# ESP12_Low_Power.net
KiCad netlist of a schematic drawn in EAGLE
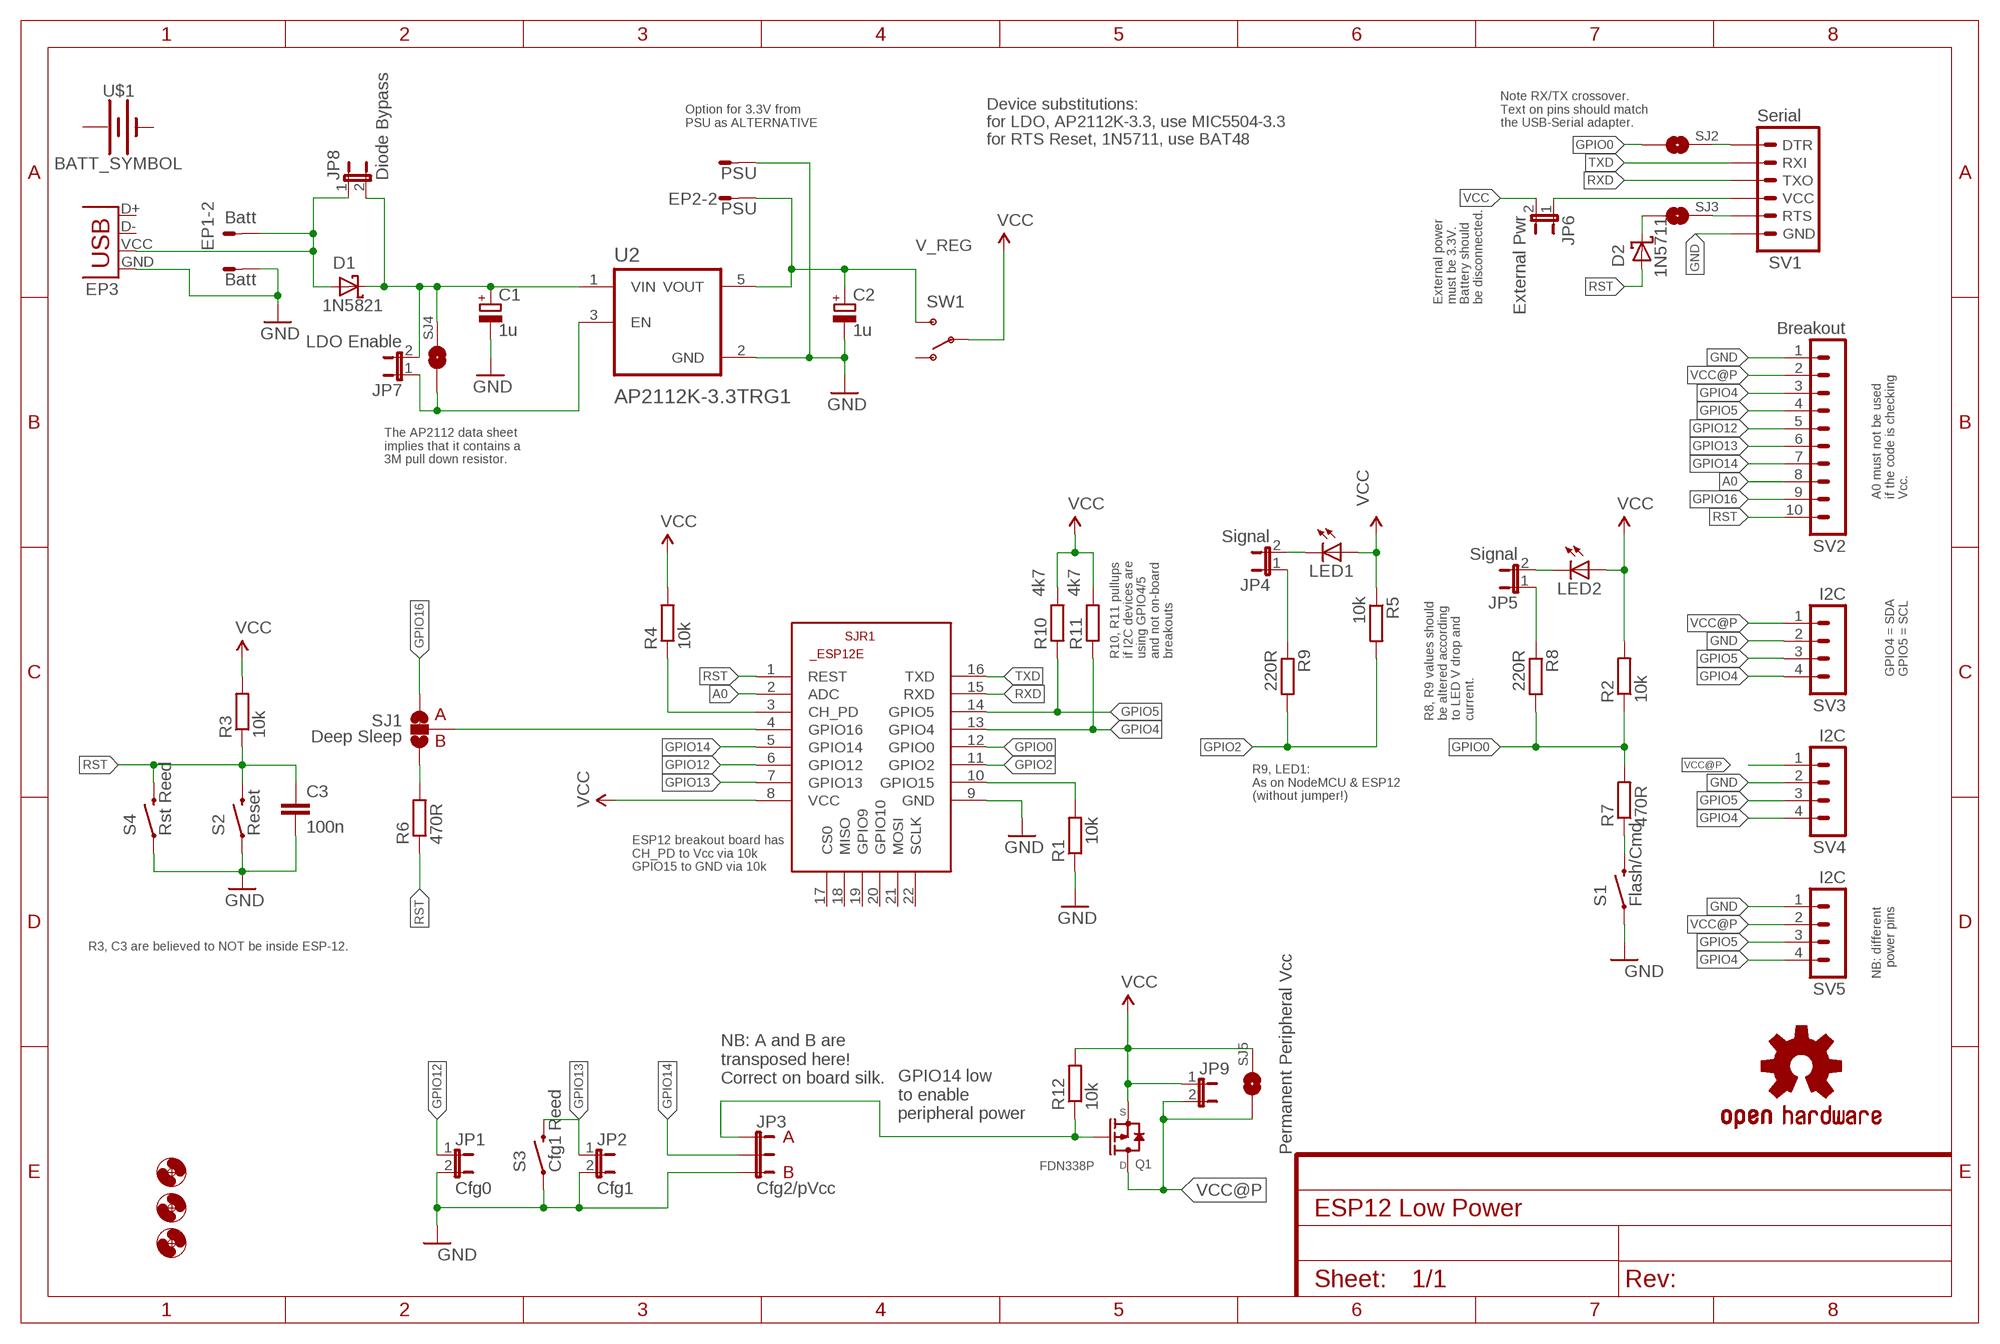
[diagram p0: schematic, sheet 1]

(export (version "E")
  (design (tool "Eeschema 10.0.6"))
  (components
    (comp (ref "C1")
      (value "1u")
      (footprint "eagle-import:E2,5-5")
      (libsource (lib "eagle-import") (part "CPOL-EUE2.5-510UF"))
    )
    (comp (ref "C2")
      (value "1u")
      (footprint "eagle-import:E2,5-5")
      (libsource (lib "eagle-import") (part "CPOL-EUE2.5-510UF"))
    )
    (comp (ref "C3")
      (value "100n")
      (footprint "eagle-import:1206")
      (libsource (lib "eagle-import") (part "C-EU1206"))
    )
    (comp (ref "D1")
      (value "1N5821")
      (footprint "eagle-import:DO201-15")
      (libsource (lib "eagle-import") (part "DIODE-SCHOTTKYDO-201-VERT"))
    )
    (comp (ref "D2")
      (value "1N5711")
      (footprint "eagle-import:DO35-7")
      (libsource (lib "eagle-import") (part "DIODE-SCHOTTKYDO35-7"))
    )
    (comp (ref "EP1")
      (value "Batt")
      (footprint "eagle-import:02P")
      (libsource (lib "eagle-import") (part "M02S"))
    )
    (comp (ref "EP2")
      (value "PSU")
      (footprint "eagle-import:02P")
      (libsource (lib "eagle-import") (part "M02S"))
    )
    (comp (ref "EP3")
      (value "USB-FCI_SMD***")
      (footprint "eagle-import:FCI_USB_B_SMD")
      (libsource (lib "eagle-import") (part "USB-FCI_SMD"))
    )
    (comp (ref "H1")
      (value "MOUNT-HOLE3.2")
      (footprint "eagle-import:3,2")
      (libsource (lib "eagle-import") (part "MOUNT-HOLE3.2"))
    )
    (comp (ref "H2")
      (value "MOUNT-HOLE3.2")
      (footprint "eagle-import:3,2")
      (libsource (lib "eagle-import") (part "MOUNT-HOLE3.2"))
    )
    (comp (ref "H4")
      (value "MOUNT-HOLE3.2")
      (footprint "eagle-import:3,2")
      (libsource (lib "eagle-import") (part "MOUNT-HOLE3.2"))
    )
    (comp (ref "JP1")
      (value "Cfg0")
      (footprint "eagle-import:1X02")
      (libsource (lib "eagle-import") (part "JUMPER-2PTH"))
    )
    (comp (ref "JP2")
      (value "Cfg1")
      (footprint "eagle-import:1X02")
      (libsource (lib "eagle-import") (part "JUMPER-2PTH"))
    )
    (comp (ref "JP3")
      (value "Cfg2/pVcc")
      (footprint "eagle-import:1X03_JMP")
      (libsource (lib "eagle-import") (part "JUMPER-3PTH"))
    )
    (comp (ref "JP4")
      (value "Signal")
      (footprint "eagle-import:1X02")
      (libsource (lib "eagle-import") (part "JUMPER-2PTH"))
    )
    (comp (ref "JP5")
      (value "Signal")
      (footprint "eagle-import:1X02")
      (libsource (lib "eagle-import") (part "JUMPER-2PTH"))
    )
    (comp (ref "JP6")
      (value "External Pwr")
      (footprint "eagle-import:1X02")
      (libsource (lib "eagle-import") (part "JUMPER-2PTH"))
    )
    (comp (ref "JP7")
      (value "LDO Enable")
      (footprint "eagle-import:1X02")
      (libsource (lib "eagle-import") (part "JUMPER-2PTH"))
    )
    (comp (ref "JP8")
      (value "Diode Bypass")
      (footprint "eagle-import:1X02")
      (libsource (lib "eagle-import") (part "JUMPER-2PTH"))
    )
    (comp (ref "JP9")
      (value "Permanent Peripheral Vcc")
      (footprint "eagle-import:1X02")
      (libsource (lib "eagle-import") (part "JUMPER-2PTH"))
    )
    (comp (ref "LED1")
      (value "LED1206")
      (footprint "eagle-import:LED-1206")
      (libsource (lib "eagle-import") (part "LED1206"))
    )
    (comp (ref "LED2")
      (value "LED1206")
      (footprint "eagle-import:LED-1206")
      (libsource (lib "eagle-import") (part "LED1206"))
    )
    (comp (ref "LOGO1")
      (value "OSHW-LOGOM")
      (footprint "eagle-import:OSHW-LOGO-M")
      (libsource (lib "eagle-import") (part "OSHW-LOGOM"))
    )
    (comp (ref "Q1")
      (value "FDN338P")
      (footprint "eagle-import:SOT23")
      (libsource (lib "eagle-import") (part "FDN338P_PMOS-SOT23"))
    )
    (comp (ref "R1")
      (value "10k")
      (footprint "eagle-import:1206")
      (libsource (lib "eagle-import") (part "R-EU_"))
    )
    (comp (ref "R2")
      (value "10k")
      (footprint "eagle-import:1206")
      (libsource (lib "eagle-import") (part "R-EU_"))
    )
    (comp (ref "R3")
      (value "10k")
      (footprint "eagle-import:1206")
      (libsource (lib "eagle-import") (part "R-EU_"))
    )
    (comp (ref "R4")
      (value "10k")
      (footprint "eagle-import:1206")
      (libsource (lib "eagle-import") (part "R-EU_"))
    )
    (comp (ref "R5")
      (value "10k")
      (footprint "eagle-import:1206")
      (libsource (lib "eagle-import") (part "R-EU_"))
    )
    (comp (ref "R6")
      (value "470R")
      (footprint "eagle-import:0204_7")
      (libsource (lib "eagle-import") (part "R-EU_0204/7"))
    )
    (comp (ref "R7")
      (value "470R")
      (footprint "eagle-import:0204_7")
      (libsource (lib "eagle-import") (part "R-EU_0204/7"))
    )
    (comp (ref "R8")
      (value "220R")
      (footprint "eagle-import:0204_7")
      (libsource (lib "eagle-import") (part "R-EU_0204/7"))
    )
    (comp (ref "R9")
      (value "220R")
      (footprint "eagle-import:0204_7")
      (libsource (lib "eagle-import") (part "R-EU_0204/7"))
    )
    (comp (ref "R10")
      (value "4k7")
      (footprint "eagle-import:1206")
      (libsource (lib "eagle-import") (part "R-EU_"))
    )
    (comp (ref "R11")
      (value "4k7")
      (footprint "eagle-import:1206")
      (libsource (lib "eagle-import") (part "R-EU_"))
    )
    (comp (ref "R12")
      (value "10k")
      (footprint "eagle-import:0204_7")
      (libsource (lib "eagle-import") (part "R-EU_0204/7"))
    )
    (comp (ref "S1")
      (value "Flash/Cmd")
      (footprint "eagle-import:TACTILE-PTH")
      (libsource (lib "eagle-import") (part "SWITCH-MOMENTARY-2PTH"))
    )
    (comp (ref "S2")
      (value "Reset")
      (footprint "eagle-import:TACTILE-PTH")
      (libsource (lib "eagle-import") (part "SWITCH-MOMENTARY-2PTH"))
    )
    (comp (ref "S3")
      (value "Cfg1 Reed")
      (footprint "eagle-import:REED_SWITCH_PTH")
      (libsource (lib "eagle-import") (part "SWITCH-MOMENTARY-2PTH_REED"))
    )
    (comp (ref "S4")
      (value "Rst Reed")
      (footprint "eagle-import:REED_SWITCH_PTH")
      (libsource (lib "eagle-import") (part "SWITCH-MOMENTARY-2PTH_REED"))
    )
    (comp (ref "SJ1")
      (value "Deep Sleep")
      (footprint "eagle-import:SJ_3")
      (libsource (lib "eagle-import") (part "SOLDERJUMPER_2WAYSJ_3_TRACE"))
    )
    (comp (ref "SJ2")
      (value "SOLDERJUMPERTRACE")
      (footprint "eagle-import:SJ_2S-TRACE")
      (libsource (lib "eagle-import") (part "SOLDERJUMPERTRACE"))
    )
    (comp (ref "SJ3")
      (value "SOLDERJUMPERTRACE")
      (footprint "eagle-import:SJ_2S-TRACE")
      (libsource (lib "eagle-import") (part "SOLDERJUMPERTRACE"))
    )
    (comp (ref "SJ4")
      (value "SOLDERJUMPERTRACE")
      (footprint "eagle-import:SJ_2S-TRACE")
      (libsource (lib "eagle-import") (part "SOLDERJUMPERTRACE"))
    )
    (comp (ref "SJ5")
      (value "SOLDERJUMPERTRACE")
      (footprint "eagle-import:SJ_2S-TRACE")
      (libsource (lib "eagle-import") (part "SOLDERJUMPERTRACE"))
    )
    (comp (ref "SJR1")
      (value "ESP8266-12EESP12E")
      (footprint "eagle-import:ESP8266-ESP12E")
      (libsource (lib "eagle-import") (part "ESP8266-12EESP12E"))
    )
    (comp (ref "SV1")
      (value "Serial")
      (footprint "eagle-import:1X06-KIT")
      (libsource (lib "eagle-import") (part "ESP8266_SERIAL_PROGRAM1X06_ESP_SERIAL"))
    )
    (comp (ref "SV2")
      (value "Breakout")
      (footprint "eagle-import:MA10-1")
      (libsource (lib "eagle-import") (part "HEADER-1X10P"))
    )
    (comp (ref "SV3")
      (value "I2C")
      (footprint "eagle-import:MA04-1")
      (libsource (lib "eagle-import") (part "MA04-1"))
    )
    (comp (ref "SV4")
      (value "I2C")
      (footprint "eagle-import:MA04-1")
      (libsource (lib "eagle-import") (part "MA04-1"))
    )
    (comp (ref "SV5")
      (value "I2C")
      (footprint "eagle-import:MA04-1")
      (libsource (lib "eagle-import") (part "MA04-1"))
    )
    (comp (ref "SW1")
      (value "SWITCH_SPDTMULTICOMP_MS2")
      (footprint "eagle-import:MULTICOMP_2MS")
      (libsource (lib "eagle-import") (part "SWITCH_SPDTMULTICOMP_MS2"))
    )
    (comp (ref "U$1")
      (value "BATT_SYMBOL")
      (footprint "eagle-import:BATTERY_18650-HOLDER_SILK")
      (libsource (lib "eagle-import") (part "BATT_SYMBOL"))
    )
    (comp (ref "U2")
      (value "AP2112K-3.3TRG1")
      (footprint "eagle-import:SOT95P285X140-5N")
      (fields (field (name "MF") "Diodes Inc."))
      (libsource (lib "eagle-import") (part "AP2112K-3.3TRG1"))
    )
  )
  (nets
    (net (code "1") (name "/V_REG") (class "Default")
      (node (ref "C2") (pin "+") (pinfunction "+_+") (pintype "passive"))
      (node (ref "EP2") (pin "2") (pinfunction "S_2") (pintype "passive"))
      (node (ref "SW1") (pin "P$3") (pinfunction "S_P$3") (pintype "passive"))
      (node (ref "U2") (pin "5") (pinfunction "VOUT_5") (pintype "power_in"))
    )
    (net (code "2") (name "A0") (class "Default")
      (node (ref "SJR1") (pin "2") (pinfunction "ADC_2") (pintype "bidirectional"))
      (node (ref "SV2") (pin "8") (pinfunction "8_8") (pintype "passive"))
    )
    (net (code "3") (name "GND") (class "Default")
      (node (ref "C1") (pin "-") (pinfunction "-_-") (pintype "passive"))
      (node (ref "C2") (pin "-") (pinfunction "-_-") (pintype "passive"))
      (node (ref "C3") (pin "2") (pinfunction "2_2") (pintype "passive"))
      (node (ref "EP1") (pin "2") (pinfunction "S_2") (pintype "passive"))
      (node (ref "EP2") (pin "1") (pinfunction "S_1") (pintype "passive"))
      (node (ref "EP3") (pin "GND") (pinfunction "GND_GND") (pintype "bidirectional"))
      (node (ref "JP1") (pin "2") (pinfunction "2_2") (pintype "passive"))
      (node (ref "JP2") (pin "2") (pinfunction "2_2") (pintype "passive"))
      (node (ref "JP3") (pin "3") (pinfunction "3_3") (pintype "passive"))
      (node (ref "R1") (pin "1") (pinfunction "1_1") (pintype "passive"))
      (node (ref "S1") (pin "1") (pinfunction "1_1") (pintype "passive"))
      (node (ref "S2") (pin "1") (pinfunction "1_1") (pintype "passive"))
      (node (ref "S3") (pin "P$1") (pinfunction "1_P$1") (pintype "passive"))
      (node (ref "S4") (pin "P$1") (pinfunction "1_P$1") (pintype "passive"))
      (node (ref "SJR1") (pin "9") (pinfunction "GND_9") (pintype "bidirectional"))
      (node (ref "SV1") (pin "1") (pinfunction "GND_1") (pintype "passive"))
      (node (ref "SV2") (pin "1") (pinfunction "1_1") (pintype "passive"))
      (node (ref "SV3") (pin "2") (pinfunction "2_2") (pintype "passive"))
      (node (ref "SV4") (pin "2") (pinfunction "2_2") (pintype "passive"))
      (node (ref "SV5") (pin "1") (pinfunction "1_1") (pintype "passive"))
      (node (ref "U2") (pin "2") (pinfunction "GND_2") (pintype "power_in"))
    )
    (net (code "4") (name "GPIO0") (class "Default")
      (node (ref "R2") (pin "1") (pinfunction "1_1") (pintype "passive"))
      (node (ref "R7") (pin "2") (pinfunction "2_2") (pintype "passive"))
      (node (ref "R8") (pin "2") (pinfunction "2_2") (pintype "passive"))
      (node (ref "SJ2") (pin "1") (pinfunction "1_1") (pintype "passive"))
      (node (ref "SJR1") (pin "12") (pinfunction "GPIO0_12") (pintype "bidirectional"))
    )
    (net (code "5") (name "GPIO2") (class "Default")
      (node (ref "R5") (pin "2") (pinfunction "2_2") (pintype "passive"))
      (node (ref "R9") (pin "2") (pinfunction "2_2") (pintype "passive"))
      (node (ref "SJR1") (pin "11") (pinfunction "GPIO2_11") (pintype "bidirectional"))
    )
    (net (code "6") (name "GPIO4") (class "Default")
      (node (ref "R11") (pin "1") (pinfunction "1_1") (pintype "passive"))
      (node (ref "SJR1") (pin "13") (pinfunction "GPIO4_13") (pintype "bidirectional"))
      (node (ref "SV2") (pin "3") (pinfunction "3_3") (pintype "passive"))
      (node (ref "SV3") (pin "4") (pinfunction "4_4") (pintype "passive"))
      (node (ref "SV4") (pin "4") (pinfunction "4_4") (pintype "passive"))
      (node (ref "SV5") (pin "4") (pinfunction "4_4") (pintype "passive"))
    )
    (net (code "7") (name "GPIO5") (class "Default")
      (node (ref "R10") (pin "1") (pinfunction "1_1") (pintype "passive"))
      (node (ref "SJR1") (pin "14") (pinfunction "GPIO5_14") (pintype "bidirectional"))
      (node (ref "SV2") (pin "4") (pinfunction "4_4") (pintype "passive"))
      (node (ref "SV3") (pin "3") (pinfunction "3_3") (pintype "passive"))
      (node (ref "SV4") (pin "3") (pinfunction "3_3") (pintype "passive"))
      (node (ref "SV5") (pin "3") (pinfunction "3_3") (pintype "passive"))
    )
    (net (code "8") (name "GPIO12") (class "Default")
      (node (ref "JP1") (pin "1") (pinfunction "1_1") (pintype "passive"))
      (node (ref "SJR1") (pin "6") (pinfunction "GPIO12_6") (pintype "bidirectional"))
      (node (ref "SV2") (pin "5") (pinfunction "5_5") (pintype "passive"))
    )
    (net (code "9") (name "GPIO13") (class "Default")
      (node (ref "JP2") (pin "1") (pinfunction "1_1") (pintype "passive"))
      (node (ref "S3") (pin "P$2") (pinfunction "2_P$2") (pintype "passive"))
      (node (ref "SJR1") (pin "7") (pinfunction "GPIO13_7") (pintype "bidirectional"))
      (node (ref "SV2") (pin "6") (pinfunction "6_6") (pintype "passive"))
    )
    (net (code "10") (name "GPIO14") (class "Default")
      (node (ref "JP3") (pin "2") (pinfunction "2_2") (pintype "passive"))
      (node (ref "SJR1") (pin "5") (pinfunction "GPIO14_5") (pintype "bidirectional"))
      (node (ref "SV2") (pin "7") (pinfunction "7_7") (pintype "passive"))
    )
    (net (code "11") (name "GPIO16") (class "Default")
      (node (ref "SJ1") (pin "1") (pinfunction "1_1") (pintype "passive"))
      (node (ref "SV2") (pin "9") (pinfunction "9_9") (pintype "passive"))
    )
    (net (code "12") (name "Net-(D2-PadC)") (class "Default")
      (node (ref "D2") (pin "C") (pinfunction "C_C") (pintype "passive"))
      (node (ref "SJ3") (pin "1") (pinfunction "1_1") (pintype "passive"))
    )
    (net (code "13") (name "Net-(EP1A-S)") (class "Default")
      (node (ref "D1") (pin "A") (pinfunction "A_A") (pintype "passive"))
      (node (ref "EP1") (pin "1") (pinfunction "S_1") (pintype "passive"))
      (node (ref "EP3") (pin "VCC") (pinfunction "VBUS_VCC") (pintype "bidirectional"))
      (node (ref "JP8") (pin "1") (pinfunction "1_1") (pintype "passive"))
    )
    (net (code "14") (name "Net-(JP4-Pad1)") (class "Default")
      (node (ref "JP4") (pin "1") (pinfunction "1_1") (pintype "passive"))
      (node (ref "R9") (pin "1") (pinfunction "1_1") (pintype "passive"))
    )
    (net (code "15") (name "Net-(JP4-Pad2)") (class "Default")
      (node (ref "JP4") (pin "2") (pinfunction "2_2") (pintype "passive"))
      (node (ref "LED1") (pin "C") (pinfunction "C_C") (pintype "passive"))
    )
    (net (code "16") (name "Net-(JP5-Pad1)") (class "Default")
      (node (ref "JP5") (pin "1") (pinfunction "1_1") (pintype "passive"))
      (node (ref "R8") (pin "1") (pinfunction "1_1") (pintype "passive"))
    )
    (net (code "17") (name "Net-(JP5-Pad2)") (class "Default")
      (node (ref "JP5") (pin "2") (pinfunction "2_2") (pintype "passive"))
      (node (ref "LED2") (pin "C") (pinfunction "C_C") (pintype "passive"))
    )
    (net (code "18") (name "Net-(Q1-G)") (class "Default")
      (node (ref "JP3") (pin "1") (pinfunction "1_1") (pintype "passive"))
      (node (ref "Q1") (pin "1") (pinfunction "G_1") (pintype "passive"))
      (node (ref "R12") (pin "1") (pinfunction "1_1") (pintype "passive"))
    )
    (net (code "19") (name "Net-(R6-Pad2)") (class "Default")
      (node (ref "R6") (pin "2") (pinfunction "2_2") (pintype "passive"))
      (node (ref "SJ1") (pin "3") (pinfunction "3_3") (pintype "passive"))
    )
    (net (code "20") (name "Net-(S1-2)") (class "Default")
      (node (ref "R7") (pin "1") (pinfunction "1_1") (pintype "passive"))
      (node (ref "S1") (pin "3") (pinfunction "2_3") (pintype "passive"))
    )
    (net (code "21") (name "Net-(SJR1-CH_PD)") (class "Default")
      (node (ref "R4") (pin "1") (pinfunction "1_1") (pintype "passive"))
      (node (ref "SJR1") (pin "3") (pinfunction "CH_PD_3") (pintype "bidirectional"))
    )
    (net (code "22") (name "Net-(SJR1-GPIO15)") (class "Default")
      (node (ref "R1") (pin "2") (pinfunction "2_2") (pintype "passive"))
      (node (ref "SJR1") (pin "10") (pinfunction "GPIO15_10") (pintype "bidirectional"))
    )
    (net (code "23") (name "Net-(SJR1-GPIO16)") (class "Default")
      (node (ref "SJ1") (pin "2") (pinfunction "2_2") (pintype "passive"))
      (node (ref "SJR1") (pin "4") (pinfunction "GPIO16_4") (pintype "bidirectional"))
    )
    (net (code "24") (name "Net-(SV1-DTR)") (class "Default")
      (node (ref "SJ2") (pin "2") (pinfunction "2_2") (pintype "passive"))
      (node (ref "SV1") (pin "6") (pinfunction "DTR_6") (pintype "passive"))
    )
    (net (code "25") (name "Net-(SV1-RTS)") (class "Default")
      (node (ref "SJ3") (pin "2") (pinfunction "2_2") (pintype "passive"))
      (node (ref "SV1") (pin "2") (pinfunction "RTS_2") (pintype "passive"))
    )
    (net (code "26") (name "Net-(SV1-VCC)") (class "Default")
      (node (ref "JP6") (pin "1") (pinfunction "1_1") (pintype "passive"))
      (node (ref "SV1") (pin "3") (pinfunction "VCC_3") (pintype "passive"))
    )
    (net (code "27") (name "Net-(U2-EN)") (class "Default")
      (node (ref "JP7") (pin "1") (pinfunction "1_1") (pintype "passive"))
      (node (ref "SJ4") (pin "1") (pinfunction "1_1") (pintype "passive"))
      (node (ref "U2") (pin "3") (pinfunction "EN_3") (pintype "input"))
    )
    (net (code "28") (name "Net-(U2-VIN)") (class "Default")
      (node (ref "C1") (pin "+") (pinfunction "+_+") (pintype "passive"))
      (node (ref "D1") (pin "C") (pinfunction "C_C") (pintype "passive"))
      (node (ref "JP7") (pin "2") (pinfunction "2_2") (pintype "passive"))
      (node (ref "JP8") (pin "2") (pinfunction "2_2") (pintype "passive"))
      (node (ref "SJ4") (pin "2") (pinfunction "2_2") (pintype "passive"))
      (node (ref "U2") (pin "1") (pinfunction "VIN_1") (pintype "power_in"))
    )
    (net (code "29") (name "RST") (class "Default")
      (node (ref "C3") (pin "1") (pinfunction "1_1") (pintype "passive"))
      (node (ref "D2") (pin "A") (pinfunction "A_A") (pintype "passive"))
      (node (ref "R3") (pin "1") (pinfunction "1_1") (pintype "passive"))
      (node (ref "R6") (pin "1") (pinfunction "1_1") (pintype "passive"))
      (node (ref "S2") (pin "3") (pinfunction "2_3") (pintype "passive"))
      (node (ref "S4") (pin "P$2") (pinfunction "2_P$2") (pintype "passive"))
      (node (ref "SJR1") (pin "1") (pinfunction "REST_1") (pintype "bidirectional"))
      (node (ref "SV2") (pin "10") (pinfunction "10_10") (pintype "passive"))
    )
    (net (code "30") (name "RXD") (class "Default")
      (node (ref "SJR1") (pin "15") (pinfunction "RXD_15") (pintype "bidirectional"))
      (node (ref "SV1") (pin "4") (pinfunction "TXO_4") (pintype "passive"))
    )
    (net (code "31") (name "TXD") (class "Default")
      (node (ref "SJR1") (pin "16") (pinfunction "TXD_16") (pintype "bidirectional"))
      (node (ref "SV1") (pin "5") (pinfunction "RXI_5") (pintype "passive"))
    )
    (net (code "32") (name "VCC") (class "Default")
      (node (ref "JP6") (pin "2") (pinfunction "2_2") (pintype "passive"))
      (node (ref "JP9") (pin "1") (pinfunction "1_1") (pintype "passive"))
      (node (ref "LED1") (pin "A") (pinfunction "A_A") (pintype "passive"))
      (node (ref "LED2") (pin "A") (pinfunction "A_A") (pintype "passive"))
      (node (ref "Q1") (pin "2") (pinfunction "S_2") (pintype "passive"))
      (node (ref "R10") (pin "2") (pinfunction "2_2") (pintype "passive"))
      (node (ref "R11") (pin "2") (pinfunction "2_2") (pintype "passive"))
      (node (ref "R12") (pin "2") (pinfunction "2_2") (pintype "passive"))
      (node (ref "R2") (pin "2") (pinfunction "2_2") (pintype "passive"))
      (node (ref "R3") (pin "2") (pinfunction "2_2") (pintype "passive"))
      (node (ref "R4") (pin "2") (pinfunction "2_2") (pintype "passive"))
      (node (ref "R5") (pin "1") (pinfunction "1_1") (pintype "passive"))
      (node (ref "SJ5") (pin "2") (pinfunction "2_2") (pintype "passive"))
      (node (ref "SJR1") (pin "8") (pinfunction "VCC_8") (pintype "bidirectional"))
      (node (ref "SW1") (pin "P$2") (pinfunction "P_P$2") (pintype "passive"))
    )
    (net (code "33") (name "VCC@P") (class "Default")
      (node (ref "JP9") (pin "2") (pinfunction "2_2") (pintype "passive"))
      (node (ref "Q1") (pin "3") (pinfunction "D_3") (pintype "passive"))
      (node (ref "SJ5") (pin "1") (pinfunction "1_1") (pintype "passive"))
      (node (ref "SV2") (pin "2") (pinfunction "2_2") (pintype "passive"))
      (node (ref "SV3") (pin "1") (pinfunction "1_1") (pintype "passive"))
      (node (ref "SV4") (pin "1") (pinfunction "1_1") (pintype "passive"))
      (node (ref "SV5") (pin "2") (pinfunction "2_2") (pintype "passive"))
    )
    (net (code "34") (name "unconnected-(EP3-PadD+)") (class "Default")
      (node (ref "EP3") (pin "D+") (pinfunction "D+_D+") (pintype "bidirectional"))
    )
    (net (code "35") (name "unconnected-(EP3-PadD-)") (class "Default")
      (node (ref "EP3") (pin "D-") (pinfunction "D-_D-") (pintype "bidirectional"))
    )
    (net (code "36") (name "unconnected-(SJR1-CS0-Pad17)") (class "Default")
      (node (ref "SJR1") (pin "17") (pinfunction "CS0_17") (pintype "bidirectional"))
    )
    (net (code "37") (name "unconnected-(SJR1-GPIO9-Pad19)") (class "Default")
      (node (ref "SJR1") (pin "19") (pinfunction "GPIO9_19") (pintype "bidirectional"))
    )
    (net (code "38") (name "unconnected-(SJR1-GPIO10-Pad20)") (class "Default")
      (node (ref "SJR1") (pin "20") (pinfunction "GPIO10_20") (pintype "bidirectional"))
    )
    (net (code "39") (name "unconnected-(SJR1-MISO-Pad18)") (class "Default")
      (node (ref "SJR1") (pin "18") (pinfunction "MISO_18") (pintype "bidirectional"))
    )
    (net (code "40") (name "unconnected-(SJR1-MOSI-Pad21)") (class "Default")
      (node (ref "SJR1") (pin "21") (pinfunction "MOSI_21") (pintype "bidirectional"))
    )
    (net (code "41") (name "unconnected-(SJR1-SCLK-Pad22)") (class "Default")
      (node (ref "SJR1") (pin "22") (pinfunction "SCLK_22") (pintype "bidirectional"))
    )
    (net (code "42") (name "unconnected-(SW1-O-PadP$1)") (class "Default")
      (node (ref "SW1") (pin "P$1") (pinfunction "O_P$1") (pintype "passive"))
    )
  )
)
